# GenericCommand.net
KiCad netlist of a schematic drawn in EAGLE
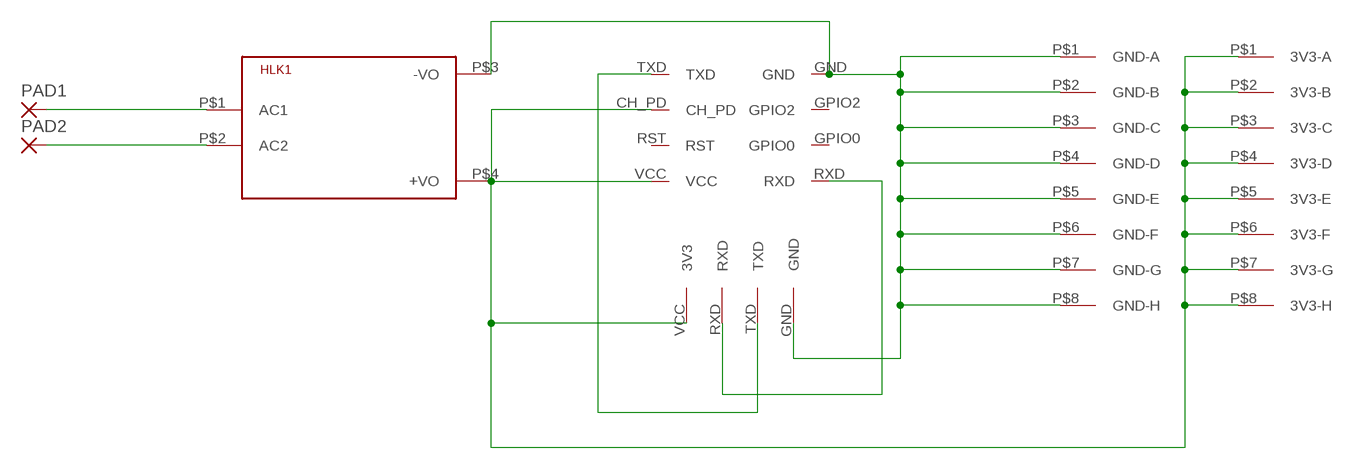
[diagram p0: schematic, sheet 1]

(export (version "E")
  (design (tool "Eeschema 10.0.6"))
  (components
    (comp (ref "HLK1")
      (value "HLK-PM013W")
      (footprint "eagle-import:HLK-PM01")
      (libsource (lib "eagle-import") (part "HLK-PM013W"))
    )
    (comp (ref "PAD1")
      (value "3,81/1,4")
      (footprint "eagle-import:3,81_1,4")
      (libsource (lib "eagle-import") (part "3,81/1,4"))
    )
    (comp (ref "PAD2")
      (value "3,81/1,4")
      (footprint "eagle-import:3,81_1,4")
      (libsource (lib "eagle-import") (part "3,81/1,4"))
    )
    (comp (ref "U$1")
      (value "ESP-01-SLOT")
      (footprint "eagle-import:ESP-01-SLOT")
      (libsource (lib "eagle-import") (part "ESP-01-SLOT"))
    )
    (comp (ref "U$2")
      (value "CP-2102-CONN")
      (footprint "eagle-import:CP-2102-CONN")
      (libsource (lib "eagle-import") (part "CP-2102-CONN"))
    )
    (comp (ref "U$3")
      (value "3V3-8")
      (footprint "eagle-import:3.3V-8")
      (libsource (lib "eagle-import") (part "3V3-8"))
    )
    (comp (ref "U$4")
      (value "GND-8")
      (footprint "eagle-import:GND-8")
      (libsource (lib "eagle-import") (part "GND-8"))
    )
  )
  (nets
    (net (code "1") (name "Net-(HLK1-+VO)") (class "Default")
      (node (ref "HLK1") (pin "P$4") (pinfunction "+VO_P$4") (pintype "bidirectional"))
      (node (ref "U$1") (pin "CH_PD") (pinfunction "CH_PD_CH_PD") (pintype "bidirectional"))
      (node (ref "U$1") (pin "VCC") (pinfunction "VCC_VCC") (pintype "bidirectional"))
      (node (ref "U$2") (pin "VCC") (pinfunction "3V3_VCC") (pintype "bidirectional"))
      (node (ref "U$3") (pin "P$1") (pinfunction "3V3-A_P$1") (pintype "bidirectional"))
      (node (ref "U$3") (pin "P$2") (pinfunction "3V3-B_P$2") (pintype "bidirectional"))
      (node (ref "U$3") (pin "P$3") (pinfunction "3V3-C_P$3") (pintype "bidirectional"))
      (node (ref "U$3") (pin "P$4") (pinfunction "3V3-D_P$4") (pintype "bidirectional"))
      (node (ref "U$3") (pin "P$5") (pinfunction "3V3-E_P$5") (pintype "bidirectional"))
      (node (ref "U$3") (pin "P$6") (pinfunction "3V3-F_P$6") (pintype "bidirectional"))
      (node (ref "U$3") (pin "P$7") (pinfunction "3V3-G_P$7") (pintype "bidirectional"))
      (node (ref "U$3") (pin "P$8") (pinfunction "3V3-H_P$8") (pintype "bidirectional"))
    )
    (net (code "2") (name "Net-(HLK1--VO)") (class "Default")
      (node (ref "HLK1") (pin "P$3") (pinfunction "-VO_P$3") (pintype "bidirectional"))
      (node (ref "U$1") (pin "GND") (pinfunction "GND_GND") (pintype "bidirectional"))
      (node (ref "U$2") (pin "GND") (pinfunction "GND_GND") (pintype "bidirectional"))
      (node (ref "U$4") (pin "P$1") (pinfunction "GND-A_P$1") (pintype "bidirectional"))
      (node (ref "U$4") (pin "P$2") (pinfunction "GND-B_P$2") (pintype "bidirectional"))
      (node (ref "U$4") (pin "P$3") (pinfunction "GND-C_P$3") (pintype "bidirectional"))
      (node (ref "U$4") (pin "P$4") (pinfunction "GND-D_P$4") (pintype "bidirectional"))
      (node (ref "U$4") (pin "P$5") (pinfunction "GND-E_P$5") (pintype "bidirectional"))
      (node (ref "U$4") (pin "P$6") (pinfunction "GND-F_P$6") (pintype "bidirectional"))
      (node (ref "U$4") (pin "P$7") (pinfunction "GND-G_P$7") (pintype "bidirectional"))
      (node (ref "U$4") (pin "P$8") (pinfunction "GND-H_P$8") (pintype "bidirectional"))
    )
    (net (code "3") (name "Net-(HLK1-AC1)") (class "Default")
      (node (ref "HLK1") (pin "P$1") (pinfunction "AC1_P$1") (pintype "bidirectional"))
      (node (ref "PAD1") (pin "1") (pinfunction "P_1") (pintype "passive"))
    )
    (net (code "4") (name "Net-(HLK1-AC2)") (class "Default")
      (node (ref "HLK1") (pin "P$2") (pinfunction "AC2_P$2") (pintype "bidirectional"))
      (node (ref "PAD2") (pin "1") (pinfunction "P_1") (pintype "passive"))
    )
    (net (code "5") (name "Net-(U$1-PadRXD)") (class "Default")
      (node (ref "U$1") (pin "RXD") (pinfunction "RXD_RXD") (pintype "bidirectional"))
      (node (ref "U$2") (pin "RXD") (pinfunction "RXD_RXD") (pintype "bidirectional"))
    )
    (net (code "6") (name "Net-(U$1-PadTXD)") (class "Default")
      (node (ref "U$1") (pin "TXD") (pinfunction "TXD_TXD") (pintype "bidirectional"))
      (node (ref "U$2") (pin "TXD") (pinfunction "TXD_TXD") (pintype "bidirectional"))
    )
    (net (code "7") (name "unconnected-(U$1-PadGPIO0)") (class "Default")
      (node (ref "U$1") (pin "GPIO0") (pinfunction "GPIO0_GPIO0") (pintype "bidirectional"))
    )
    (net (code "8") (name "unconnected-(U$1-PadGPIO2)") (class "Default")
      (node (ref "U$1") (pin "GPIO2") (pinfunction "GPIO2_GPIO2") (pintype "bidirectional"))
    )
    (net (code "9") (name "unconnected-(U$1-PadRST)") (class "Default")
      (node (ref "U$1") (pin "RST") (pinfunction "RST_RST") (pintype "bidirectional"))
    )
  )
)
